# fabflash-mk-2_3-controller.net
KiCad netlist of a schematic drawn in EAGLE
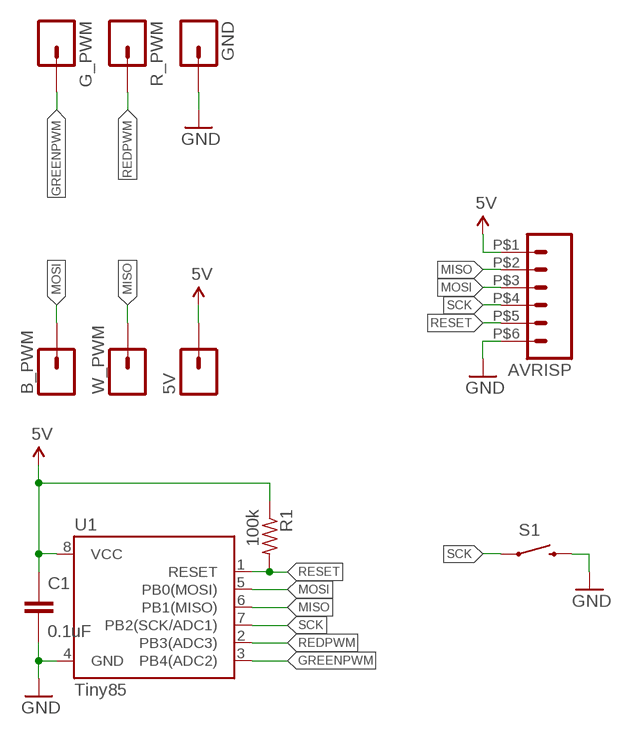
[diagram p0: schematic, sheet 1]

(export (version "E")
  (design (tool "Eeschema 10.0.6"))
  (components
    (comp (ref "5V")
      (value "M01PTH-0.9MM")
      (footprint "eagle-import:1X01-0.9MM")
      (libsource (lib "eagle-import") (part "M01PTH-0.9MM"))
    )
    (comp (ref "AVRISP")
      (value "M06PTH-2MM-NS")
      (footprint "eagle-import:1X06-PTH-2MM-NS")
      (libsource (lib "eagle-import") (part "M06PTH-2MM-NS"))
    )
    (comp (ref "B_PWM")
      (value "M01PTH-0.9MM")
      (footprint "eagle-import:1X01-0.9MM")
      (libsource (lib "eagle-import") (part "M01PTH-0.9MM"))
    )
    (comp (ref "C1")
      (value "0.1uF")
      (footprint "eagle-import:C0603")
      (libsource (lib "eagle-import") (part "CAPACITOR-CERAMICC0603"))
    )
    (comp (ref "GND")
      (value "M01PTH-0.9MM")
      (footprint "eagle-import:1X01-0.9MM")
      (libsource (lib "eagle-import") (part "M01PTH-0.9MM"))
    )
    (comp (ref "G_PWM")
      (value "M01PTH-0.9MM")
      (footprint "eagle-import:1X01-0.9MM")
      (libsource (lib "eagle-import") (part "M01PTH-0.9MM"))
    )
    (comp (ref "R1")
      (value "100k")
      (footprint "eagle-import:R0603")
      (libsource (lib "eagle-import") (part "RESISTORR0603"))
    )
    (comp (ref "R_PWM")
      (value "M01PTH-0.9MM")
      (footprint "eagle-import:1X01-0.9MM")
      (libsource (lib "eagle-import") (part "M01PTH-0.9MM"))
    )
    (comp (ref "S1")
      (value "SWITCH-MOMENTARY-2PTH")
      (footprint "eagle-import:TACTILE-PTH")
      (libsource (lib "eagle-import") (part "SWITCH-MOMENTARY-2PTH"))
    )
    (comp (ref "U1")
      (value "Tiny85")
      (footprint "eagle-import:SO08-EIAJ")
      (libsource (lib "eagle-import") (part "ATTINY45TINY85-20-SOICW"))
    )
    (comp (ref "W_PWM")
      (value "M01PTH-0.9MM")
      (footprint "eagle-import:1X01-0.9MM")
      (libsource (lib "eagle-import") (part "M01PTH-0.9MM"))
    )
  )
  (nets
    (net (code "1") (name "5V") (class "Default")
      (node (ref "5V") (pin "1") (pinfunction "1_1") (pintype "passive"))
      (node (ref "AVRISP") (pin "P$1") (pinfunction "1_P$1") (pintype "passive"))
      (node (ref "C1") (pin "1") (pinfunction "1_1") (pintype "passive"))
      (node (ref "R1") (pin "1") (pinfunction "1_1") (pintype "passive"))
      (node (ref "U1") (pin "8") (pinfunction "VCC_8") (pintype "bidirectional"))
    )
    (net (code "2") (name "GND") (class "Default")
      (node (ref "AVRISP") (pin "P$6") (pinfunction "6_P$6") (pintype "passive"))
      (node (ref "C1") (pin "2") (pinfunction "2_2") (pintype "passive"))
      (node (ref "GND") (pin "1") (pinfunction "1_1") (pintype "passive"))
      (node (ref "S1") (pin "3") (pinfunction "2_3") (pintype "passive"))
      (node (ref "S1") (pin "4") (pinfunction "2_4") (pintype "passive"))
      (node (ref "U1") (pin "4") (pinfunction "GND_4") (pintype "bidirectional"))
    )
    (net (code "3") (name "GREENPWM") (class "Default")
      (node (ref "G_PWM") (pin "1") (pinfunction "1_1") (pintype "passive"))
      (node (ref "U1") (pin "3") (pinfunction "PB4(ADC2)_3") (pintype "bidirectional"))
    )
    (net (code "4") (name "MISO") (class "Default")
      (node (ref "AVRISP") (pin "P$2") (pinfunction "2_P$2") (pintype "passive"))
      (node (ref "U1") (pin "6") (pinfunction "PB1(MISO)_6") (pintype "bidirectional"))
      (node (ref "W_PWM") (pin "1") (pinfunction "1_1") (pintype "passive"))
    )
    (net (code "5") (name "MOSI") (class "Default")
      (node (ref "AVRISP") (pin "P$3") (pinfunction "3_P$3") (pintype "passive"))
      (node (ref "B_PWM") (pin "1") (pinfunction "1_1") (pintype "passive"))
      (node (ref "U1") (pin "5") (pinfunction "PB0(MOSI)_5") (pintype "bidirectional"))
    )
    (net (code "6") (name "REDPWM") (class "Default")
      (node (ref "R_PWM") (pin "1") (pinfunction "1_1") (pintype "passive"))
      (node (ref "U1") (pin "2") (pinfunction "PB3(ADC3)_2") (pintype "bidirectional"))
    )
    (net (code "7") (name "RESET") (class "Default")
      (node (ref "AVRISP") (pin "P$5") (pinfunction "5_P$5") (pintype "passive"))
      (node (ref "R1") (pin "2") (pinfunction "2_2") (pintype "passive"))
      (node (ref "U1") (pin "1") (pinfunction "RESET_1") (pintype "bidirectional"))
    )
    (net (code "8") (name "SCK") (class "Default")
      (node (ref "AVRISP") (pin "P$4") (pinfunction "4_P$4") (pintype "passive"))
      (node (ref "S1") (pin "1") (pinfunction "1_1") (pintype "passive"))
      (node (ref "S1") (pin "2") (pinfunction "1_2") (pintype "passive"))
      (node (ref "U1") (pin "7") (pinfunction "PB2(SCK/ADC1)_7") (pintype "bidirectional"))
    )
  )
)
